# mav_nus_breakout.net
KiCad netlist of a schematic drawn in EAGLE
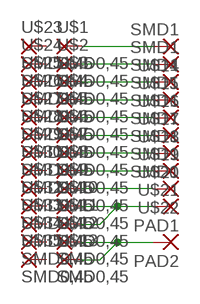
[diagram p0: schematic, sheet 1]

(export (version "E")
  (design (tool "Eeschema 10.0.6"))
  (components
    (comp (ref "PAD1")
      (value "SMD2")
      (footprint "eagle-import:SMD1,27-2,54")
      (libsource (lib "eagle-import") (part "SMD2"))
    )
    (comp (ref "PAD2")
      (value "SMD2")
      (footprint "eagle-import:SMD1,27-2,54")
      (libsource (lib "eagle-import") (part "SMD2"))
    )
    (comp (ref "U$1")
      (value "SMD0,45")
      (footprint "eagle-import:SMD0,45-1,35")
      (libsource (lib "eagle-import") (part "SMD0,45"))
    )
    (comp (ref "U$2")
      (value "SMD0,45")
      (footprint "eagle-import:SMD0,45-1,35")
      (libsource (lib "eagle-import") (part "SMD0,45"))
    )
    (comp (ref "U$3")
      (value "SMD0,45")
      (footprint "eagle-import:SMD0,45-1,35")
      (libsource (lib "eagle-import") (part "SMD0,45"))
    )
    (comp (ref "U$4")
      (value "SMD0,45")
      (footprint "eagle-import:SMD0,45-1,35")
      (libsource (lib "eagle-import") (part "SMD0,45"))
    )
    (comp (ref "U$5")
      (value "SMD0,45")
      (footprint "eagle-import:SMD0,45-1,35")
      (libsource (lib "eagle-import") (part "SMD0,45"))
    )
    (comp (ref "U$6")
      (value "SMD0,45")
      (footprint "eagle-import:SMD0,45-1,35")
      (libsource (lib "eagle-import") (part "SMD0,45"))
    )
    (comp (ref "U$7")
      (value "SMD0,45")
      (footprint "eagle-import:SMD0,45-1,35")
      (libsource (lib "eagle-import") (part "SMD0,45"))
    )
    (comp (ref "U$8")
      (value "SMD0,45")
      (footprint "eagle-import:SMD0,45-1,35")
      (libsource (lib "eagle-import") (part "SMD0,45"))
    )
    (comp (ref "U$9")
      (value "SMD0,45")
      (footprint "eagle-import:SMD0,45-1,35")
      (libsource (lib "eagle-import") (part "SMD0,45"))
    )
    (comp (ref "U$10")
      (value "SMD0,45")
      (footprint "eagle-import:SMD0,45-1,35")
      (libsource (lib "eagle-import") (part "SMD0,45"))
    )
    (comp (ref "U$11")
      (value "SMD0,45")
      (footprint "eagle-import:SMD0,45-1,35")
      (libsource (lib "eagle-import") (part "SMD0,45"))
    )
    (comp (ref "U$12")
      (value "SMD0,45")
      (footprint "eagle-import:SMD0,45-1,35")
      (libsource (lib "eagle-import") (part "SMD0,45"))
    )
    (comp (ref "U$13")
      (value "SMD0,45")
      (footprint "eagle-import:SMD0,45-1,35")
      (libsource (lib "eagle-import") (part "SMD0,45"))
    )
    (comp (ref "U$14")
      (value "SMD1")
      (footprint "eagle-import:SMD0,8-1,6")
      (libsource (lib "eagle-import") (part "SMD1"))
    )
    (comp (ref "U$15")
      (value "SMD1")
      (footprint "eagle-import:SMD0,8-1,6")
      (libsource (lib "eagle-import") (part "SMD1"))
    )
    (comp (ref "U$16")
      (value "SMD1")
      (footprint "eagle-import:SMD0,8-1,6")
      (libsource (lib "eagle-import") (part "SMD1"))
    )
    (comp (ref "U$17")
      (value "SMD1")
      (footprint "eagle-import:SMD0,8-1,6")
      (libsource (lib "eagle-import") (part "SMD1"))
    )
    (comp (ref "U$18")
      (value "SMD1")
      (footprint "eagle-import:SMD0,8-1,6")
      (libsource (lib "eagle-import") (part "SMD1"))
    )
    (comp (ref "U$19")
      (value "SMD1")
      (footprint "eagle-import:SMD0,8-1,6")
      (libsource (lib "eagle-import") (part "SMD1"))
    )
    (comp (ref "U$20")
      (value "SMD1")
      (footprint "eagle-import:SMD0,8-1,6")
      (libsource (lib "eagle-import") (part "SMD1"))
    )
    (comp (ref "U$21")
      (value "SMD1")
      (footprint "eagle-import:SMD0,8-1,6")
      (libsource (lib "eagle-import") (part "SMD1"))
    )
    (comp (ref "U$22")
      (value "SMD1")
      (footprint "eagle-import:SMD0,8-1,6")
      (libsource (lib "eagle-import") (part "SMD1"))
    )
    (comp (ref "U$23")
      (value "SMD0,45")
      (footprint "eagle-import:SMD0,45-1,35")
      (libsource (lib "eagle-import") (part "SMD0,45"))
    )
    (comp (ref "U$24")
      (value "SMD0,45")
      (footprint "eagle-import:SMD0,45-1,35")
      (libsource (lib "eagle-import") (part "SMD0,45"))
    )
    (comp (ref "U$25")
      (value "SMD0,45")
      (footprint "eagle-import:SMD0,45-1,35")
      (libsource (lib "eagle-import") (part "SMD0,45"))
    )
    (comp (ref "U$26")
      (value "SMD0,45")
      (footprint "eagle-import:SMD0,45-1,35")
      (libsource (lib "eagle-import") (part "SMD0,45"))
    )
    (comp (ref "U$27")
      (value "SMD0,45")
      (footprint "eagle-import:SMD0,45-1,35")
      (libsource (lib "eagle-import") (part "SMD0,45"))
    )
    (comp (ref "U$28")
      (value "SMD0,45")
      (footprint "eagle-import:SMD0,45-1,35")
      (libsource (lib "eagle-import") (part "SMD0,45"))
    )
    (comp (ref "U$29")
      (value "SMD0,45")
      (footprint "eagle-import:SMD0,45-1,35")
      (libsource (lib "eagle-import") (part "SMD0,45"))
    )
    (comp (ref "U$30")
      (value "SMD0,45")
      (footprint "eagle-import:SMD0,45-1,35")
      (libsource (lib "eagle-import") (part "SMD0,45"))
    )
    (comp (ref "U$31")
      (value "SMD0,45")
      (footprint "eagle-import:SMD0,45-1,35")
      (libsource (lib "eagle-import") (part "SMD0,45"))
    )
    (comp (ref "U$32")
      (value "SMD0,45")
      (footprint "eagle-import:SMD0,45-1,35")
      (libsource (lib "eagle-import") (part "SMD0,45"))
    )
    (comp (ref "U$33")
      (value "SMD0,45")
      (footprint "eagle-import:SMD0,45-1,35")
      (libsource (lib "eagle-import") (part "SMD0,45"))
    )
    (comp (ref "U$34")
      (value "SMD0,45")
      (footprint "eagle-import:SMD0,45-1,35")
      (libsource (lib "eagle-import") (part "SMD0,45"))
    )
    (comp (ref "U$35")
      (value "SMD0,45")
      (footprint "eagle-import:SMD0,45-1,35")
      (libsource (lib "eagle-import") (part "SMD0,45"))
    )
  )
  (nets
    (net (code "1") (name "Net-(PAD1-P)") (class "Default")
      (node (ref "PAD1") (pin "1") (pinfunction "P_1") (pintype "passive"))
      (node (ref "U$10") (pin "P$1") (pinfunction "P_P$1") (pintype "passive"))
      (node (ref "U$11") (pin "P$1") (pinfunction "P_P$1") (pintype "passive"))
    )
    (net (code "2") (name "Net-(PAD2-P)") (class "Default")
      (node (ref "PAD2") (pin "1") (pinfunction "P_1") (pintype "passive"))
      (node (ref "U$12") (pin "P$1") (pinfunction "P_P$1") (pintype "passive"))
      (node (ref "U$13") (pin "P$1") (pinfunction "P_P$1") (pintype "passive"))
    )
    (net (code "3") (name "Net-(U$1-P)") (class "Default")
      (node (ref "U$1") (pin "P$1") (pinfunction "P_P$1") (pintype "passive"))
      (node (ref "U$14") (pin "P$1") (pinfunction "P_P$1") (pintype "passive"))
    )
    (net (code "4") (name "Net-(U$15-P)") (class "Default")
      (node (ref "U$15") (pin "P$1") (pinfunction "P_P$1") (pintype "passive"))
      (node (ref "U$2") (pin "P$1") (pinfunction "P_P$1") (pintype "passive"))
    )
    (net (code "5") (name "Net-(U$16-P)") (class "Default")
      (node (ref "U$16") (pin "P$1") (pinfunction "P_P$1") (pintype "passive"))
      (node (ref "U$3") (pin "P$1") (pinfunction "P_P$1") (pintype "passive"))
    )
    (net (code "6") (name "Net-(U$17-P)") (class "Default")
      (node (ref "U$17") (pin "P$1") (pinfunction "P_P$1") (pintype "passive"))
      (node (ref "U$4") (pin "P$1") (pinfunction "P_P$1") (pintype "passive"))
    )
    (net (code "7") (name "Net-(U$18-P)") (class "Default")
      (node (ref "U$18") (pin "P$1") (pinfunction "P_P$1") (pintype "passive"))
      (node (ref "U$5") (pin "P$1") (pinfunction "P_P$1") (pintype "passive"))
    )
    (net (code "8") (name "Net-(U$19-P)") (class "Default")
      (node (ref "U$19") (pin "P$1") (pinfunction "P_P$1") (pintype "passive"))
      (node (ref "U$6") (pin "P$1") (pinfunction "P_P$1") (pintype "passive"))
    )
    (net (code "9") (name "Net-(U$20-P)") (class "Default")
      (node (ref "U$20") (pin "P$1") (pinfunction "P_P$1") (pintype "passive"))
      (node (ref "U$7") (pin "P$1") (pinfunction "P_P$1") (pintype "passive"))
    )
    (net (code "10") (name "Net-(U$21-P)") (class "Default")
      (node (ref "U$21") (pin "P$1") (pinfunction "P_P$1") (pintype "passive"))
      (node (ref "U$8") (pin "P$1") (pinfunction "P_P$1") (pintype "passive"))
    )
    (net (code "11") (name "Net-(U$22-P)") (class "Default")
      (node (ref "U$22") (pin "P$1") (pinfunction "P_P$1") (pintype "passive"))
      (node (ref "U$9") (pin "P$1") (pinfunction "P_P$1") (pintype "passive"))
    )
    (net (code "12") (name "unconnected-(U$23-P-PadP$1)") (class "Default")
      (node (ref "U$23") (pin "P$1") (pinfunction "P_P$1") (pintype "passive"))
    )
    (net (code "13") (name "unconnected-(U$24-P-PadP$1)") (class "Default")
      (node (ref "U$24") (pin "P$1") (pinfunction "P_P$1") (pintype "passive"))
    )
    (net (code "14") (name "unconnected-(U$25-P-PadP$1)") (class "Default")
      (node (ref "U$25") (pin "P$1") (pinfunction "P_P$1") (pintype "passive"))
    )
    (net (code "15") (name "unconnected-(U$26-P-PadP$1)") (class "Default")
      (node (ref "U$26") (pin "P$1") (pinfunction "P_P$1") (pintype "passive"))
    )
    (net (code "16") (name "unconnected-(U$27-P-PadP$1)") (class "Default")
      (node (ref "U$27") (pin "P$1") (pinfunction "P_P$1") (pintype "passive"))
    )
    (net (code "17") (name "unconnected-(U$28-P-PadP$1)") (class "Default")
      (node (ref "U$28") (pin "P$1") (pinfunction "P_P$1") (pintype "passive"))
    )
    (net (code "18") (name "unconnected-(U$29-P-PadP$1)") (class "Default")
      (node (ref "U$29") (pin "P$1") (pinfunction "P_P$1") (pintype "passive"))
    )
    (net (code "19") (name "unconnected-(U$30-P-PadP$1)") (class "Default")
      (node (ref "U$30") (pin "P$1") (pinfunction "P_P$1") (pintype "passive"))
    )
    (net (code "20") (name "unconnected-(U$31-P-PadP$1)") (class "Default")
      (node (ref "U$31") (pin "P$1") (pinfunction "P_P$1") (pintype "passive"))
    )
    (net (code "21") (name "unconnected-(U$32-P-PadP$1)") (class "Default")
      (node (ref "U$32") (pin "P$1") (pinfunction "P_P$1") (pintype "passive"))
    )
    (net (code "22") (name "unconnected-(U$33-P-PadP$1)") (class "Default")
      (node (ref "U$33") (pin "P$1") (pinfunction "P_P$1") (pintype "passive"))
    )
    (net (code "23") (name "unconnected-(U$34-P-PadP$1)") (class "Default")
      (node (ref "U$34") (pin "P$1") (pinfunction "P_P$1") (pintype "passive"))
    )
    (net (code "24") (name "unconnected-(U$35-P-PadP$1)") (class "Default")
      (node (ref "U$35") (pin "P$1") (pinfunction "P_P$1") (pintype "passive"))
    )
  )
)
